# encoder_only_board.net
KiCad netlist of a schematic drawn in EAGLE
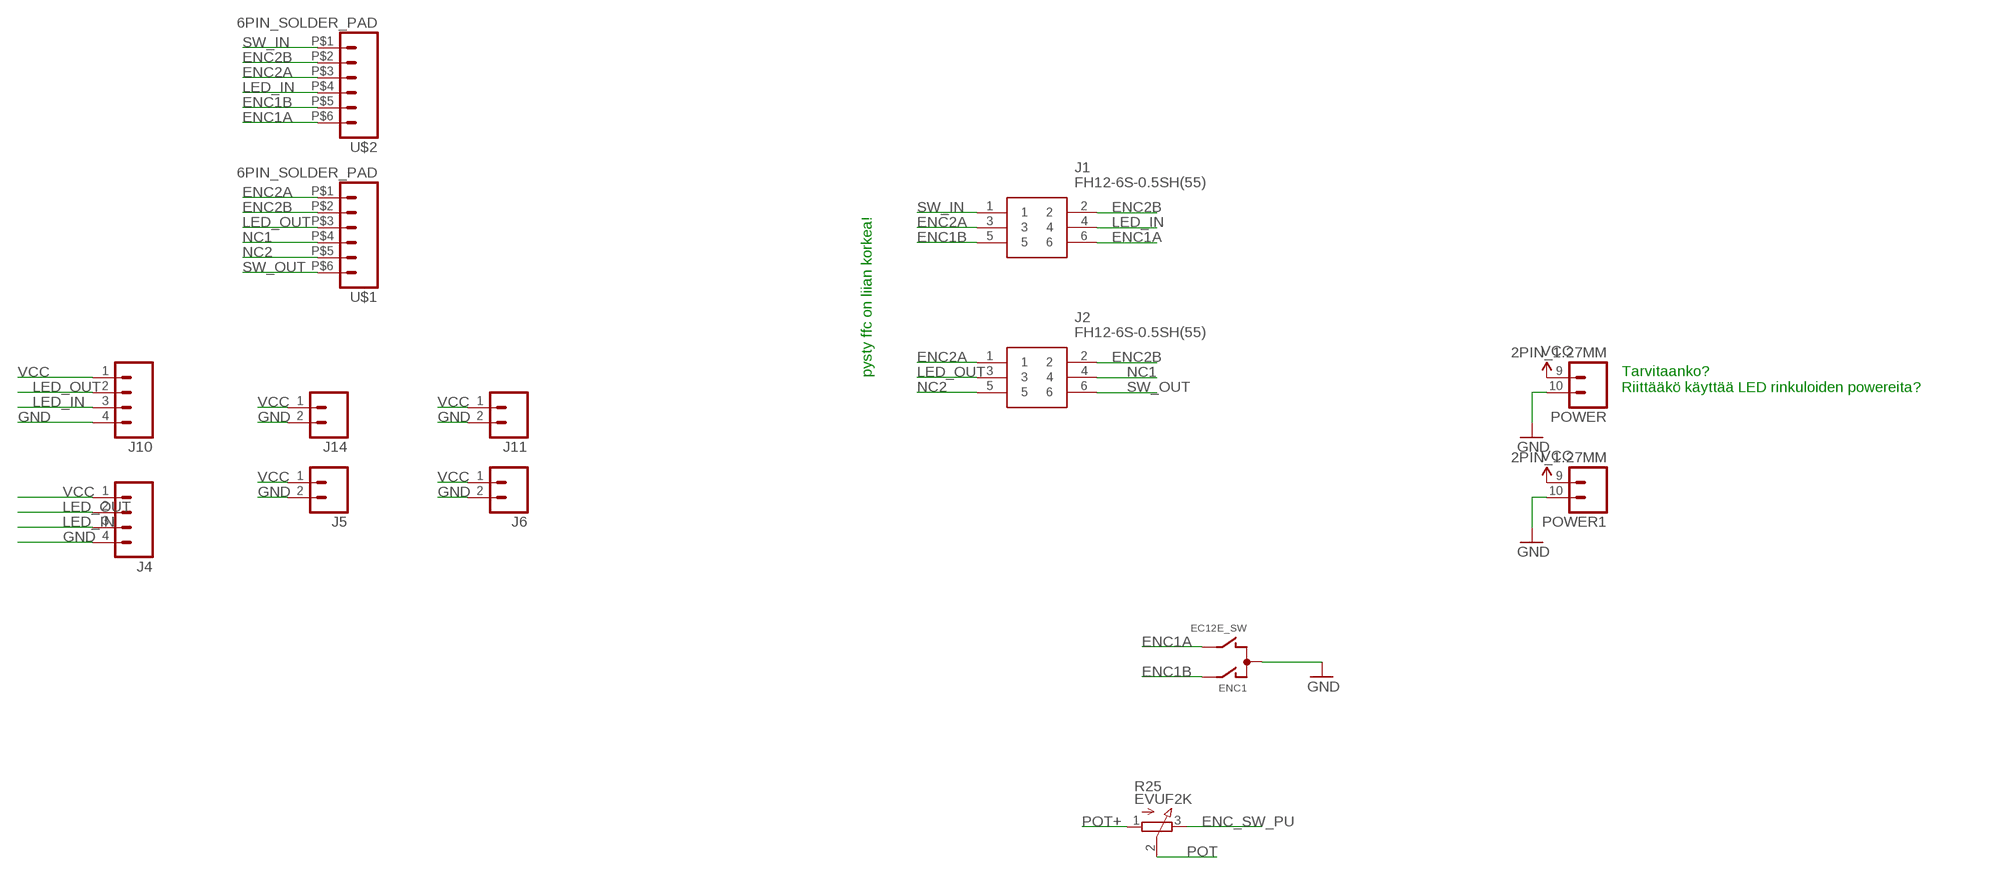
[diagram p0: schematic, sheet 1]
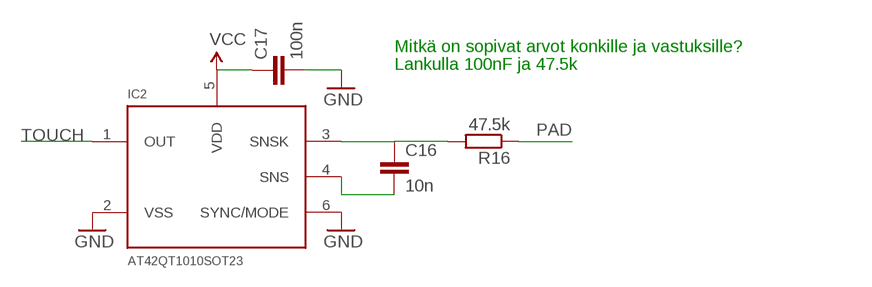
[diagram p1: schematic, sheet 2]
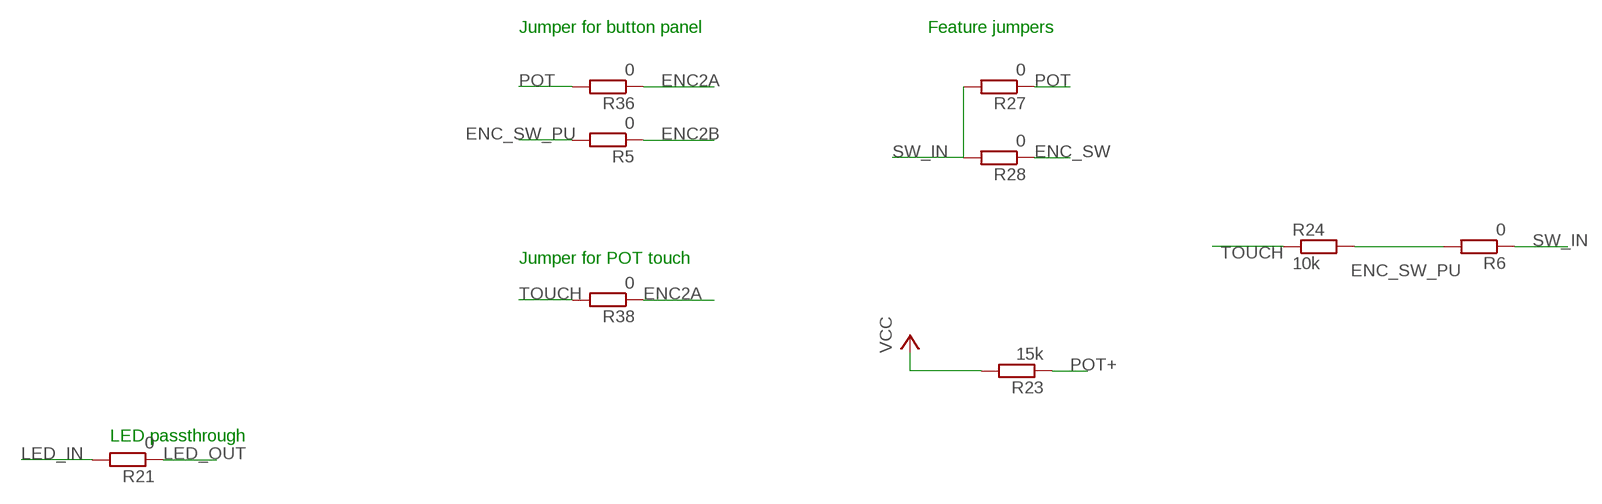
[diagram p2: schematic, sheet 3]
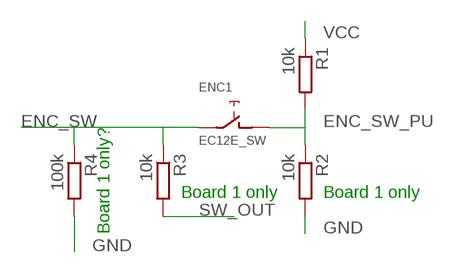
[diagram p3: schematic, sheet 4]

(export (version "E")
  (design (tool "Eeschema 10.0.6"))
  (components
    (comp (ref "C16")
      (value "10n")
      (footprint "eagle-import:0603-CAP")
      (libsource (lib "eagle-import") (part "CAP0603-CAP"))
    )
    (comp (ref "C17")
      (value "100n")
      (footprint "eagle-import:0603-CAP")
      (libsource (lib "eagle-import") (part "CAP0603-CAP"))
    )
    (comp (ref "IC2")
      (value "AT42QT1010SOT23")
      (footprint "eagle-import:SOT23-6")
      (libsource (lib "eagle-import") (part "AT42QT1010SOT23"))
    )
    (comp (ref "R16")
      (value "47.5k")
      (footprint "eagle-import:R0603")
      (libsource (lib "eagle-import") (part "R-EU_R0603"))
    )
    (comp (ref "R5")
      (value "0")
      (footprint "eagle-import:R0603")
      (fields (field (name "SPICEPREFIX") "R"))
      (libsource (lib "eagle-import") (part "R-EU_R0603"))
    )
    (comp (ref "R6")
      (value "0")
      (footprint "eagle-import:R0603")
      (fields (field (name "SPICEPREFIX") "R"))
      (libsource (lib "eagle-import") (part "R-EU_R0603"))
    )
    (comp (ref "R21")
      (value "0")
      (footprint "eagle-import:R0603")
      (libsource (lib "eagle-import") (part "R-EU_R0603"))
    )
    (comp (ref "R23")
      (value "15k")
      (footprint "eagle-import:R0603")
      (fields (field (name "SPICEPREFIX") "R"))
      (libsource (lib "eagle-import") (part "R-EU_R0603"))
    )
    (comp (ref "R24")
      (value "10k")
      (footprint "eagle-import:R0603")
      (fields (field (name "SPICEPREFIX") "R"))
      (libsource (lib "eagle-import") (part "R-EU_R0603"))
    )
    (comp (ref "R27")
      (value "0")
      (footprint "eagle-import:R0603")
      (fields (field (name "SPICEPREFIX") "R"))
      (libsource (lib "eagle-import") (part "R-EU_R0603"))
    )
    (comp (ref "R28")
      (value "0")
      (footprint "eagle-import:R0603")
      (fields (field (name "SPICEPREFIX") "R"))
      (libsource (lib "eagle-import") (part "R-EU_R0603"))
    )
    (comp (ref "R36")
      (value "0")
      (footprint "eagle-import:R0603")
      (fields (field (name "SPICEPREFIX") "R"))
      (libsource (lib "eagle-import") (part "R-EU_R0603"))
    )
    (comp (ref "R38")
      (value "0")
      (footprint "eagle-import:R0603")
      (fields (field (name "SPICEPREFIX") "R"))
      (libsource (lib "eagle-import") (part "R-EU_R0603"))
    )
    (comp (ref "ENC1")
      (value "EC12E_SW")
      (footprint "eagle-import:ALPS_EC12E_SW")
      (fields (field (name "MPN") "EC12E2424407"))
      (libsource (lib "eagle-import") (part "EC12E_SW"))
    )
    (comp (ref "R1")
      (value "10k")
      (footprint "eagle-import:R0603")
      (fields (field (name "SPICEPREFIX") "R"))
      (libsource (lib "eagle-import") (part "R-EU_R0603"))
    )
    (comp (ref "R2")
      (value "10k")
      (footprint "eagle-import:R0603")
      (fields (field (name "SPICEPREFIX") "R"))
      (libsource (lib "eagle-import") (part "R-EU_R0603"))
    )
    (comp (ref "R3")
      (value "10k")
      (footprint "eagle-import:R0603")
      (fields (field (name "SPICEPREFIX") "R"))
      (libsource (lib "eagle-import") (part "R-EU_R0603"))
    )
    (comp (ref "R4")
      (value "100k")
      (footprint "eagle-import:R0603")
      (fields (field (name "SPICEPREFIX") "R"))
      (libsource (lib "eagle-import") (part "R-EU_R0603"))
    )
    (comp (ref "J1")
      (value "FH12-6S-0.5SH(55)")
      (footprint "eagle-import:FH12-6S-0.5SH(55)_1")
      (fields
        (field (name "MOUSER_PART_NUMBER") "798-FH12-6S-0.5SH55")
        (field (name "RS_PART_NUMBER") "7388811P")
      )
      (libsource (lib "eagle-import") (part "FH12-6S-0.5SH(55)"))
    )
    (comp (ref "J2")
      (value "FH12-6S-0.5SH(55)")
      (footprint "eagle-import:FH12-6S-0.5SH(55)_1")
      (fields
        (field (name "MOUSER_PART_NUMBER") "798-FH12-6S-0.5SH55")
        (field (name "RS_PART_NUMBER") "7388811P")
      )
      (libsource (lib "eagle-import") (part "FH12-6S-0.5SH(55)"))
    )
    (comp (ref "J4")
      (value "M04NO_SILK_ALL_ROUND")
      (footprint "eagle-import:1X04_NO_SILK_ALL_ROUND")
      (libsource (lib "eagle-import") (part "M04NO_SILK_ALL_ROUND"))
    )
    (comp (ref "J5")
      (value "M021X02_NO_SILK")
      (footprint "eagle-import:1X02_NO_SILK")
      (libsource (lib "eagle-import") (part "M021X02_NO_SILK"))
    )
    (comp (ref "J6")
      (value "M021X02_NO_SILK")
      (footprint "eagle-import:1X02_NO_SILK")
      (libsource (lib "eagle-import") (part "M021X02_NO_SILK"))
    )
    (comp (ref "J10")
      (value "M04NO_SILK_ALL_ROUND")
      (footprint "eagle-import:1X04_NO_SILK_ALL_ROUND")
      (libsource (lib "eagle-import") (part "M04NO_SILK_ALL_ROUND"))
    )
    (comp (ref "J11")
      (value "M021X02_NO_SILK")
      (footprint "eagle-import:1X02_NO_SILK")
      (libsource (lib "eagle-import") (part "M021X02_NO_SILK"))
    )
    (comp (ref "J14")
      (value "M021X02_NO_SILK")
      (footprint "eagle-import:1X02_NO_SILK")
      (libsource (lib "eagle-import") (part "M021X02_NO_SILK"))
    )
    (comp (ref "POWER")
      (value "2PIN_1.27MM")
      (footprint "eagle-import:1X02_1.27MM_NO_SILK")
      (libsource (lib "eagle-import") (part "2PIN_1.27MM"))
    )
    (comp (ref "POWER1")
      (value "2PIN_1.27MM")
      (footprint "eagle-import:1X02_1.27MM_NO_SILK")
      (libsource (lib "eagle-import") (part "2PIN_1.27MM"))
    )
    (comp (ref "R25")
      (value "EVUF2K")
      (footprint "eagle-import:EVUFXK")
      (libsource (lib "eagle-import") (part "EVUF2K"))
    )
    (comp (ref "U$1")
      (value "6PIN_SOLDER_PAD")
      (footprint "eagle-import:6PIN_SOLDER_PAD")
      (libsource (lib "eagle-import") (part "6PIN_SOLDER_PAD"))
    )
    (comp (ref "U$2")
      (value "6PIN_SOLDER_PAD")
      (footprint "eagle-import:6PIN_SOLDER_PAD")
      (libsource (lib "eagle-import") (part "6PIN_SOLDER_PAD"))
    )
  )
  (nets
    (net (code "1") (name "ENC1A") (class "Default")
      (node (ref "ENC1") (pin "B") (pinfunction "B_B") (pintype "passive"))
      (node (ref "J1") (pin "6") (pinfunction "6_6") (pintype "bidirectional"))
      (node (ref "U$2") (pin "P$6") (pinfunction "6_P$6") (pintype "passive"))
    )
    (net (code "2") (name "ENC1B") (class "Default")
      (node (ref "ENC1") (pin "A") (pinfunction "A_A") (pintype "passive"))
      (node (ref "J1") (pin "5") (pinfunction "5_5") (pintype "bidirectional"))
      (node (ref "U$2") (pin "P$5") (pinfunction "5_P$5") (pintype "passive"))
    )
    (net (code "3") (name "ENC2A") (class "Default")
      (node (ref "J1") (pin "3") (pinfunction "3_3") (pintype "bidirectional"))
      (node (ref "J2") (pin "1") (pinfunction "1_1") (pintype "bidirectional"))
      (node (ref "R36") (pin "1") (pinfunction "1_1") (pintype "passive"))
      (node (ref "R38") (pin "1") (pinfunction "1_1") (pintype "passive"))
      (node (ref "U$1") (pin "P$1") (pinfunction "1_P$1") (pintype "passive"))
      (node (ref "U$2") (pin "P$3") (pinfunction "3_P$3") (pintype "passive"))
    )
    (net (code "4") (name "ENC2B") (class "Default")
      (node (ref "J1") (pin "2") (pinfunction "2_2") (pintype "bidirectional"))
      (node (ref "J2") (pin "2") (pinfunction "2_2") (pintype "bidirectional"))
      (node (ref "R5") (pin "1") (pinfunction "1_1") (pintype "passive"))
      (node (ref "U$1") (pin "P$2") (pinfunction "2_P$2") (pintype "passive"))
      (node (ref "U$2") (pin "P$2") (pinfunction "2_P$2") (pintype "passive"))
    )
    (net (code "5") (name "ENC_SW") (class "Default")
      (node (ref "ENC1") (pin "E") (pinfunction "2_E") (pintype "passive"))
      (node (ref "R28") (pin "1") (pinfunction "1_1") (pintype "passive"))
      (node (ref "R3") (pin "1") (pinfunction "1_1") (pintype "passive"))
      (node (ref "R4") (pin "1") (pinfunction "1_1") (pintype "passive"))
    )
    (net (code "6") (name "ENC_SW_PU") (class "Default")
      (node (ref "ENC1") (pin "D") (pinfunction "1_D") (pintype "passive"))
      (node (ref "R1") (pin "2") (pinfunction "2_2") (pintype "passive"))
      (node (ref "R2") (pin "1") (pinfunction "1_1") (pintype "passive"))
      (node (ref "R24") (pin "2") (pinfunction "2_2") (pintype "passive"))
      (node (ref "R25") (pin "3") (pinfunction "E_3") (pintype "passive"))
      (node (ref "R5") (pin "2") (pinfunction "2_2") (pintype "passive"))
      (node (ref "R6") (pin "2") (pinfunction "2_2") (pintype "passive"))
    )
    (net (code "7") (name "GND") (class "Default")
      (node (ref "C17") (pin "2") (pinfunction "2_2") (pintype "passive"))
      (node (ref "ENC1") (pin "C") (pinfunction "C_C") (pintype "passive"))
      (node (ref "IC2") (pin "2") (pinfunction "VSS_2") (pintype "bidirectional"))
      (node (ref "IC2") (pin "6") (pinfunction "SYNC/MODE_6") (pintype "bidirectional"))
      (node (ref "J10") (pin "4") (pinfunction "4_4") (pintype "passive"))
      (node (ref "J11") (pin "2") (pinfunction "2_2") (pintype "passive"))
      (node (ref "J14") (pin "2") (pinfunction "2_2") (pintype "passive"))
      (node (ref "J4") (pin "4") (pinfunction "4_4") (pintype "passive"))
      (node (ref "J5") (pin "2") (pinfunction "2_2") (pintype "passive"))
      (node (ref "J6") (pin "2") (pinfunction "2_2") (pintype "passive"))
      (node (ref "POWER") (pin "10") (pinfunction "2_10") (pintype "passive"))
      (node (ref "POWER1") (pin "10") (pinfunction "2_10") (pintype "passive"))
      (node (ref "R2") (pin "2") (pinfunction "2_2") (pintype "passive"))
      (node (ref "R4") (pin "2") (pinfunction "2_2") (pintype "passive"))
    )
    (net (code "8") (name "LED_IN") (class "Default")
      (node (ref "J1") (pin "4") (pinfunction "4_4") (pintype "bidirectional"))
      (node (ref "J10") (pin "3") (pinfunction "3_3") (pintype "passive"))
      (node (ref "J4") (pin "3") (pinfunction "3_3") (pintype "passive"))
      (node (ref "R21") (pin "2") (pinfunction "2_2") (pintype "passive"))
      (node (ref "U$2") (pin "P$4") (pinfunction "4_P$4") (pintype "passive"))
    )
    (net (code "9") (name "LED_OUT") (class "Default")
      (node (ref "J10") (pin "2") (pinfunction "2_2") (pintype "passive"))
      (node (ref "J2") (pin "3") (pinfunction "3_3") (pintype "bidirectional"))
      (node (ref "J4") (pin "2") (pinfunction "2_2") (pintype "passive"))
      (node (ref "R21") (pin "1") (pinfunction "1_1") (pintype "passive"))
      (node (ref "U$1") (pin "P$3") (pinfunction "3_P$3") (pintype "passive"))
    )
    (net (code "10") (name "NC1") (class "Default")
      (node (ref "J2") (pin "4") (pinfunction "4_4") (pintype "bidirectional"))
      (node (ref "U$1") (pin "P$4") (pinfunction "4_P$4") (pintype "passive"))
    )
    (net (code "11") (name "NC2") (class "Default")
      (node (ref "J2") (pin "5") (pinfunction "5_5") (pintype "bidirectional"))
      (node (ref "U$1") (pin "P$5") (pinfunction "5_P$5") (pintype "passive"))
    )
    (net (code "12") (name "Net-(IC2-SNS)") (class "Default")
      (node (ref "C16") (pin "2") (pinfunction "2_2") (pintype "passive"))
      (node (ref "IC2") (pin "4") (pinfunction "SNS_4") (pintype "bidirectional"))
    )
    (net (code "13") (name "Net-(IC2-SNSK)") (class "Default")
      (node (ref "C16") (pin "1") (pinfunction "1_1") (pintype "passive"))
      (node (ref "IC2") (pin "3") (pinfunction "SNSK_3") (pintype "bidirectional"))
      (node (ref "R16") (pin "2") (pinfunction "2_2") (pintype "passive"))
    )
    (net (code "14") (name "PAD") (class "Default")
      (node (ref "R16") (pin "1") (pinfunction "1_1") (pintype "passive"))
    )
    (net (code "15") (name "POT") (class "Default")
      (node (ref "R25") (pin "2") (pinfunction "S_2") (pintype "passive"))
      (node (ref "R27") (pin "1") (pinfunction "1_1") (pintype "passive"))
      (node (ref "R36") (pin "2") (pinfunction "2_2") (pintype "passive"))
    )
    (net (code "16") (name "POT+") (class "Default")
      (node (ref "R23") (pin "1") (pinfunction "1_1") (pintype "passive"))
      (node (ref "R25") (pin "1") (pinfunction "A_1") (pintype "passive"))
    )
    (net (code "17") (name "SW_IN") (class "Default")
      (node (ref "J1") (pin "1") (pinfunction "1_1") (pintype "bidirectional"))
      (node (ref "R27") (pin "2") (pinfunction "2_2") (pintype "passive"))
      (node (ref "R28") (pin "2") (pinfunction "2_2") (pintype "passive"))
      (node (ref "R6") (pin "1") (pinfunction "1_1") (pintype "passive"))
      (node (ref "U$2") (pin "P$1") (pinfunction "1_P$1") (pintype "passive"))
    )
    (net (code "18") (name "SW_OUT") (class "Default")
      (node (ref "J2") (pin "6") (pinfunction "6_6") (pintype "bidirectional"))
      (node (ref "R3") (pin "2") (pinfunction "2_2") (pintype "passive"))
      (node (ref "U$1") (pin "P$6") (pinfunction "6_P$6") (pintype "passive"))
    )
    (net (code "19") (name "TOUCH") (class "Default")
      (node (ref "IC2") (pin "1") (pinfunction "OUT_1") (pintype "bidirectional"))
      (node (ref "R24") (pin "1") (pinfunction "1_1") (pintype "passive"))
      (node (ref "R38") (pin "2") (pinfunction "2_2") (pintype "passive"))
    )
    (net (code "20") (name "VCC") (class "Default")
      (node (ref "C17") (pin "1") (pinfunction "1_1") (pintype "passive"))
      (node (ref "IC2") (pin "5") (pinfunction "VDD_5") (pintype "bidirectional"))
      (node (ref "J10") (pin "1") (pinfunction "1_1") (pintype "passive"))
      (node (ref "J11") (pin "1") (pinfunction "1_1") (pintype "passive"))
      (node (ref "J14") (pin "1") (pinfunction "1_1") (pintype "passive"))
      (node (ref "J4") (pin "1") (pinfunction "1_1") (pintype "passive"))
      (node (ref "J5") (pin "1") (pinfunction "1_1") (pintype "passive"))
      (node (ref "J6") (pin "1") (pinfunction "1_1") (pintype "passive"))
      (node (ref "POWER") (pin "9") (pinfunction "1_9") (pintype "passive"))
      (node (ref "POWER1") (pin "9") (pinfunction "1_9") (pintype "passive"))
      (node (ref "R1") (pin "1") (pinfunction "1_1") (pintype "passive"))
      (node (ref "R23") (pin "2") (pinfunction "2_2") (pintype "passive"))
    )
  )
)
